# Power.net
KiCad netlist of a schematic drawn in Altium Designer
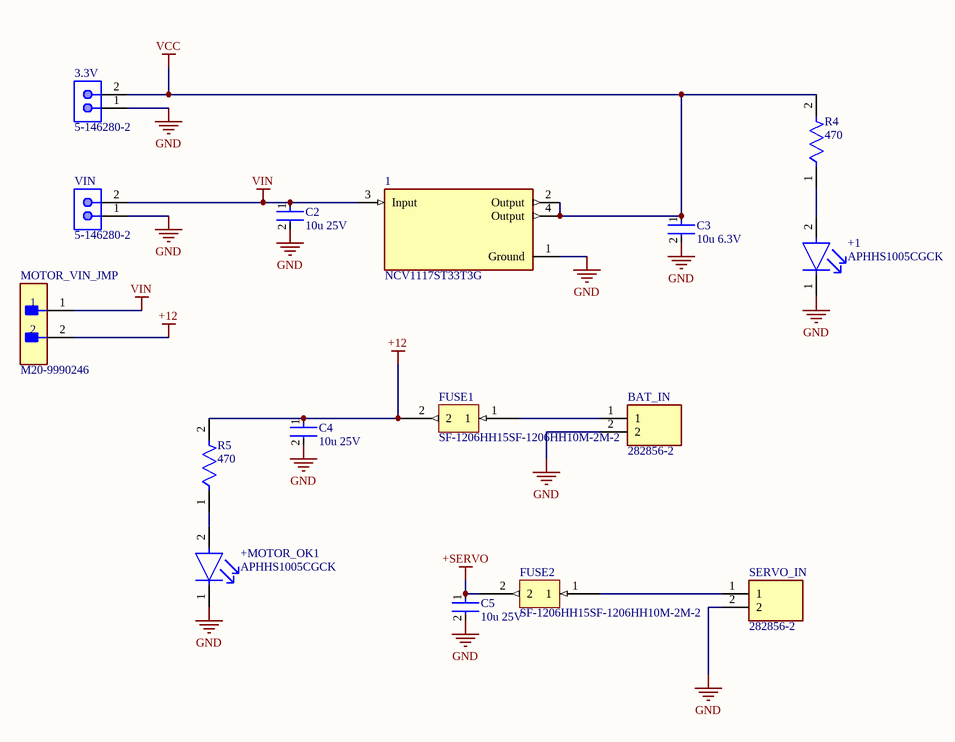
[diagram p0: Power.SchDoc]

(export (version "E")
  (design (tool "Eeschema 10.0.6"))
  (components
    (comp (ref "+1")
      (value "APHHS1005CGCK")
      (footprint "FP-APHHS1005CGCK-MFG")
      (description "LED GREEN CLEAR CHIP SMD")
      (libsource (lib "Altium Content Vault") (part "8706943c75ba83719d021d2fdc84c58"))
    )
    (comp (ref "+MOTOR_OK1")
      (value "APHHS1005CGCK")
      (footprint "FP-APHHS1005CGCK-MFG")
      (description "LED GREEN CLEAR CHIP SMD")
      (libsource (lib "Altium Content Vault") (part "8706943c75ba83719d021d2fdc84c58"))
    )
    (comp (ref "1")
      (value "NCV1117ST33T3G")
      (footprint "FP-318H-MFG")
      (description "IC REG LINEAR 3.3V 1A SOT223")
      (fields
        (field (name "OCTOPART") "https://octopart.com/ncv1117st33t3g-on+semiconductor-1215835")
        (field (name "MANUFACTURER") "ON Semiconductor")
      )
      (libsource (lib "Altium Content Vault") (part "fe1c1c19b4622c016f317b32cf6f7fc"))
    )
    (comp (ref "3.3V")
      (value "5-146280-2")
      (footprint "TECO-5-146280-2_V")
      (fields (field (name "MANUFACTURER") "TE Connectivity"))
      (libsource (lib "Altium Content Vault") (part "CN-1P-M-R2"))
    )
    (comp (ref "BAT_IN")
      (value "282856-2")
      (footprint "TE_282856-2")
      (description "TERMI-BLOK PCB MOUNT 2P")
      (fields (field (name "MF") "TE Connectivity") (field (name "DIGI-KEY_PART_NUMBER") "A98108-ND"))
      (libsource (lib "Politechnika Wrocławska") (part "282856-2"))
    )
    (comp (ref "C2")
      (value "10u 25V")
      (footprint "FP-GRM21B-0_15-IPC_C")
      (description "Chip Multilayer Ceramic Capacitors for General Purpose, 0805, 10uF, X5R, 15%, 10%, 25V")
      (fields (field (name "VOLTAGE") "25V") (field (name "TOLERANCE") "10%"))
      (libsource (lib "Altium Content Vault") (part "b4654b650e69147ec39a6b967a45e02"))
    )
    (comp (ref "C3")
      (value "10u 6.3V")
      (footprint "FP-GRM155-0_05-MFG")
      (description "Chip Multilayer Ceramic Capacitors for General Purpose, 0402, 390pF, C0G, 30ppm/°C, 5%, 50V")
      (fields (field (name "TOLERANCE") "5%") (field (name "VOLTAGE") "50V"))
      (libsource (lib "Altium Content Vault") (part "02cd4be3c70576c341d710602a673aa"))
    )
    (comp (ref "C4")
      (value "10u 25V")
      (footprint "FP-GRM21B-0_15-IPC_C")
      (description "Chip Multilayer Ceramic Capacitors for General Purpose, 0805, 10uF, X5R, 15%, 10%, 25V")
      (fields (field (name "VOLTAGE") "25V") (field (name "TOLERANCE") "10%"))
      (libsource (lib "Altium Content Vault") (part "b4654b650e69147ec39a6b967a45e02"))
    )
    (comp (ref "C5")
      (value "10u 25V")
      (footprint "FP-GRM21B-0_15-IPC_C")
      (description "Chip Multilayer Ceramic Capacitors for General Purpose, 0805, 10uF, X5R, 15%, 10%, 25V")
      (fields (field (name "VOLTAGE") "25V") (field (name "TOLERANCE") "10%"))
      (libsource (lib "Altium Content Vault") (part "b4654b650e69147ec39a6b967a45e02"))
    )
    (comp (ref "FUSE1")
      (value "SF-1206HH15SF-1206HH10M-2M-2")
      (footprint "RESC3216X12N")
      (description "Fuse Chip 10A 24VDC High Current and High Inrush Current Withstand 2-Pin SMD T/R")
      (libsource (lib "Politechnika Wrocławska") (part "SF-1206HH15M-2-Symbol-1"))
    )
    (comp (ref "FUSE2")
      (value "SF-1206HH15SF-1206HH10M-2M-2")
      (footprint "RESC3216X12N")
      (description "Fuse Chip 10A 24VDC High Current and High Inrush Current Withstand 2-Pin SMD T/R")
      (libsource (lib "Politechnika Wrocławska") (part "SF-1206HH15M-2-Symbol-1"))
    )
    (comp (ref "MOTOR_VIN_JMP")
      (value "M20-9990246")
      (footprint "FP-M20-9990246-MFG")
      (description "CONN HEADER VERT 2POS 2.54MM")
      (fields
        (field (name "OCTOPART") "https://octopart.com/m20-9990246-harwin-2590635")
        (field (name "MANUFACTURER") "Harwin")
      )
      (libsource (lib "Altium Content Vault") (part "3bc925449376181038e59eaffc5286c"))
    )
    (comp (ref "R4")
      (value "470")
      (footprint "FP-CRCW0402-e3-IPC_C")
      (description "RES Thick Film, 0Ω, 0.063W, 0402")
      (fields (field (name "TOLERANCE") "5%"))
      (libsource (lib "Altium Content Vault") (part "1029c3af85768c4190bb7ad29bc67b5"))
    )
    (comp (ref "R5")
      (value "470")
      (footprint "FP-CRCW0402-e3-IPC_C")
      (description "RES Thick Film, 0Ω, 0.063W, 0402")
      (fields (field (name "TOLERANCE") "5%"))
      (libsource (lib "Altium Content Vault") (part "1029c3af85768c4190bb7ad29bc67b5"))
    )
    (comp (ref "SERVO_IN")
      (value "282856-2")
      (footprint "TE_282856-2")
      (description "TERMI-BLOK PCB MOUNT 2P")
      (fields (field (name "MF") "TE Connectivity") (field (name "DIGI-KEY_PART_NUMBER") "A98108-ND"))
      (libsource (lib "Politechnika Wrocławska") (part "282856-2"))
    )
    (comp (ref "VIN")
      (value "5-146280-2")
      (footprint "TECO-5-146280-2_V")
      (fields (field (name "MANUFACTURER") "TE Connectivity"))
      (libsource (lib "Altium Content Vault") (part "CN-1P-M-R2"))
    )
  )
  (nets
    (net (code "1") (name "+12") (class "Default")
      (node (ref "C4") (pin "1") (pinfunction "1_1") (pintype "passive"))
      (node (ref "FUSE1") (pin "2") (pinfunction "2_2") (pintype "output"))
      (node (ref "MOTOR_VIN_JMP") (pin "2") (pinfunction "2_2") (pintype "passive"))
      (node (ref "R5") (pin "2") (pinfunction "2_2") (pintype "passive"))
    )
    (net (code "2") (name "+SERVO") (class "Default")
      (node (ref "C5") (pin "1") (pinfunction "1_1") (pintype "passive"))
      (node (ref "FUSE2") (pin "2") (pinfunction "2_2") (pintype "output"))
    )
    (net (code "3") (name "GND") (class "Default")
      (node (ref "+1") (pin "1") (pinfunction "C_1") (pintype "passive"))
      (node (ref "+MOTOR_OK1") (pin "1") (pinfunction "C_1") (pintype "passive"))
      (node (ref "1") (pin "1") (pinfunction "Ground_1") (pintype "power_in"))
      (node (ref "3.3V") (pin "1") (pinfunction "1_1") (pintype "passive"))
      (node (ref "BAT_IN") (pin "2") (pinfunction "2_2") (pintype "passive"))
      (node (ref "C2") (pin "2") (pinfunction "2_2") (pintype "passive"))
      (node (ref "C3") (pin "2") (pinfunction "2_2") (pintype "passive"))
      (node (ref "C4") (pin "2") (pinfunction "2_2") (pintype "passive"))
      (node (ref "C5") (pin "2") (pinfunction "2_2") (pintype "passive"))
      (node (ref "SERVO_IN") (pin "2") (pinfunction "2_2") (pintype "passive"))
      (node (ref "VIN") (pin "1") (pinfunction "1_1") (pintype "passive"))
    )
    (net (code "4") (name "Net-(+1-A)") (class "Default")
      (node (ref "+1") (pin "2") (pinfunction "A_2") (pintype "passive"))
      (node (ref "R4") (pin "1") (pinfunction "1_1") (pintype "passive"))
    )
    (net (code "5") (name "Net-(+MOTOR_OK1-A)") (class "Default")
      (node (ref "+MOTOR_OK1") (pin "2") (pinfunction "A_2") (pintype "passive"))
      (node (ref "R5") (pin "1") (pinfunction "1_1") (pintype "passive"))
    )
    (net (code "6") (name "Net-(BAT_IN-Pad1)") (class "Default")
      (node (ref "BAT_IN") (pin "1") (pinfunction "1_1") (pintype "passive"))
      (node (ref "FUSE1") (pin "1") (pinfunction "1_1") (pintype "input"))
    )
    (net (code "7") (name "Net-(FUSE2-Pad1)") (class "Default")
      (node (ref "FUSE2") (pin "1") (pinfunction "1_1") (pintype "input"))
      (node (ref "SERVO_IN") (pin "1") (pinfunction "1_1") (pintype "passive"))
    )
    (net (code "8") (name "VCC") (class "Default")
      (node (ref "1") (pin "2") (pinfunction "Output_2") (pintype "output"))
      (node (ref "1") (pin "4") (pinfunction "Output_4") (pintype "output"))
      (node (ref "3.3V") (pin "2") (pinfunction "2_2") (pintype "passive"))
      (node (ref "C3") (pin "1") (pinfunction "1_1") (pintype "passive"))
      (node (ref "R4") (pin "2") (pinfunction "2_2") (pintype "passive"))
    )
    (net (code "9") (name "VIN") (class "Default")
      (node (ref "1") (pin "3") (pinfunction "Input_3") (pintype "input"))
      (node (ref "C2") (pin "1") (pinfunction "1_1") (pintype "passive"))
      (node (ref "MOTOR_VIN_JMP") (pin "1") (pinfunction "1_1") (pintype "passive"))
      (node (ref "VIN") (pin "2") (pinfunction "2_2") (pintype "passive"))
    )
  )
)
